# S7CAS-PLEIADES-CARTE-MERE_P06_MISC.net
KiCad netlist of a schematic drawn in Altium Designer
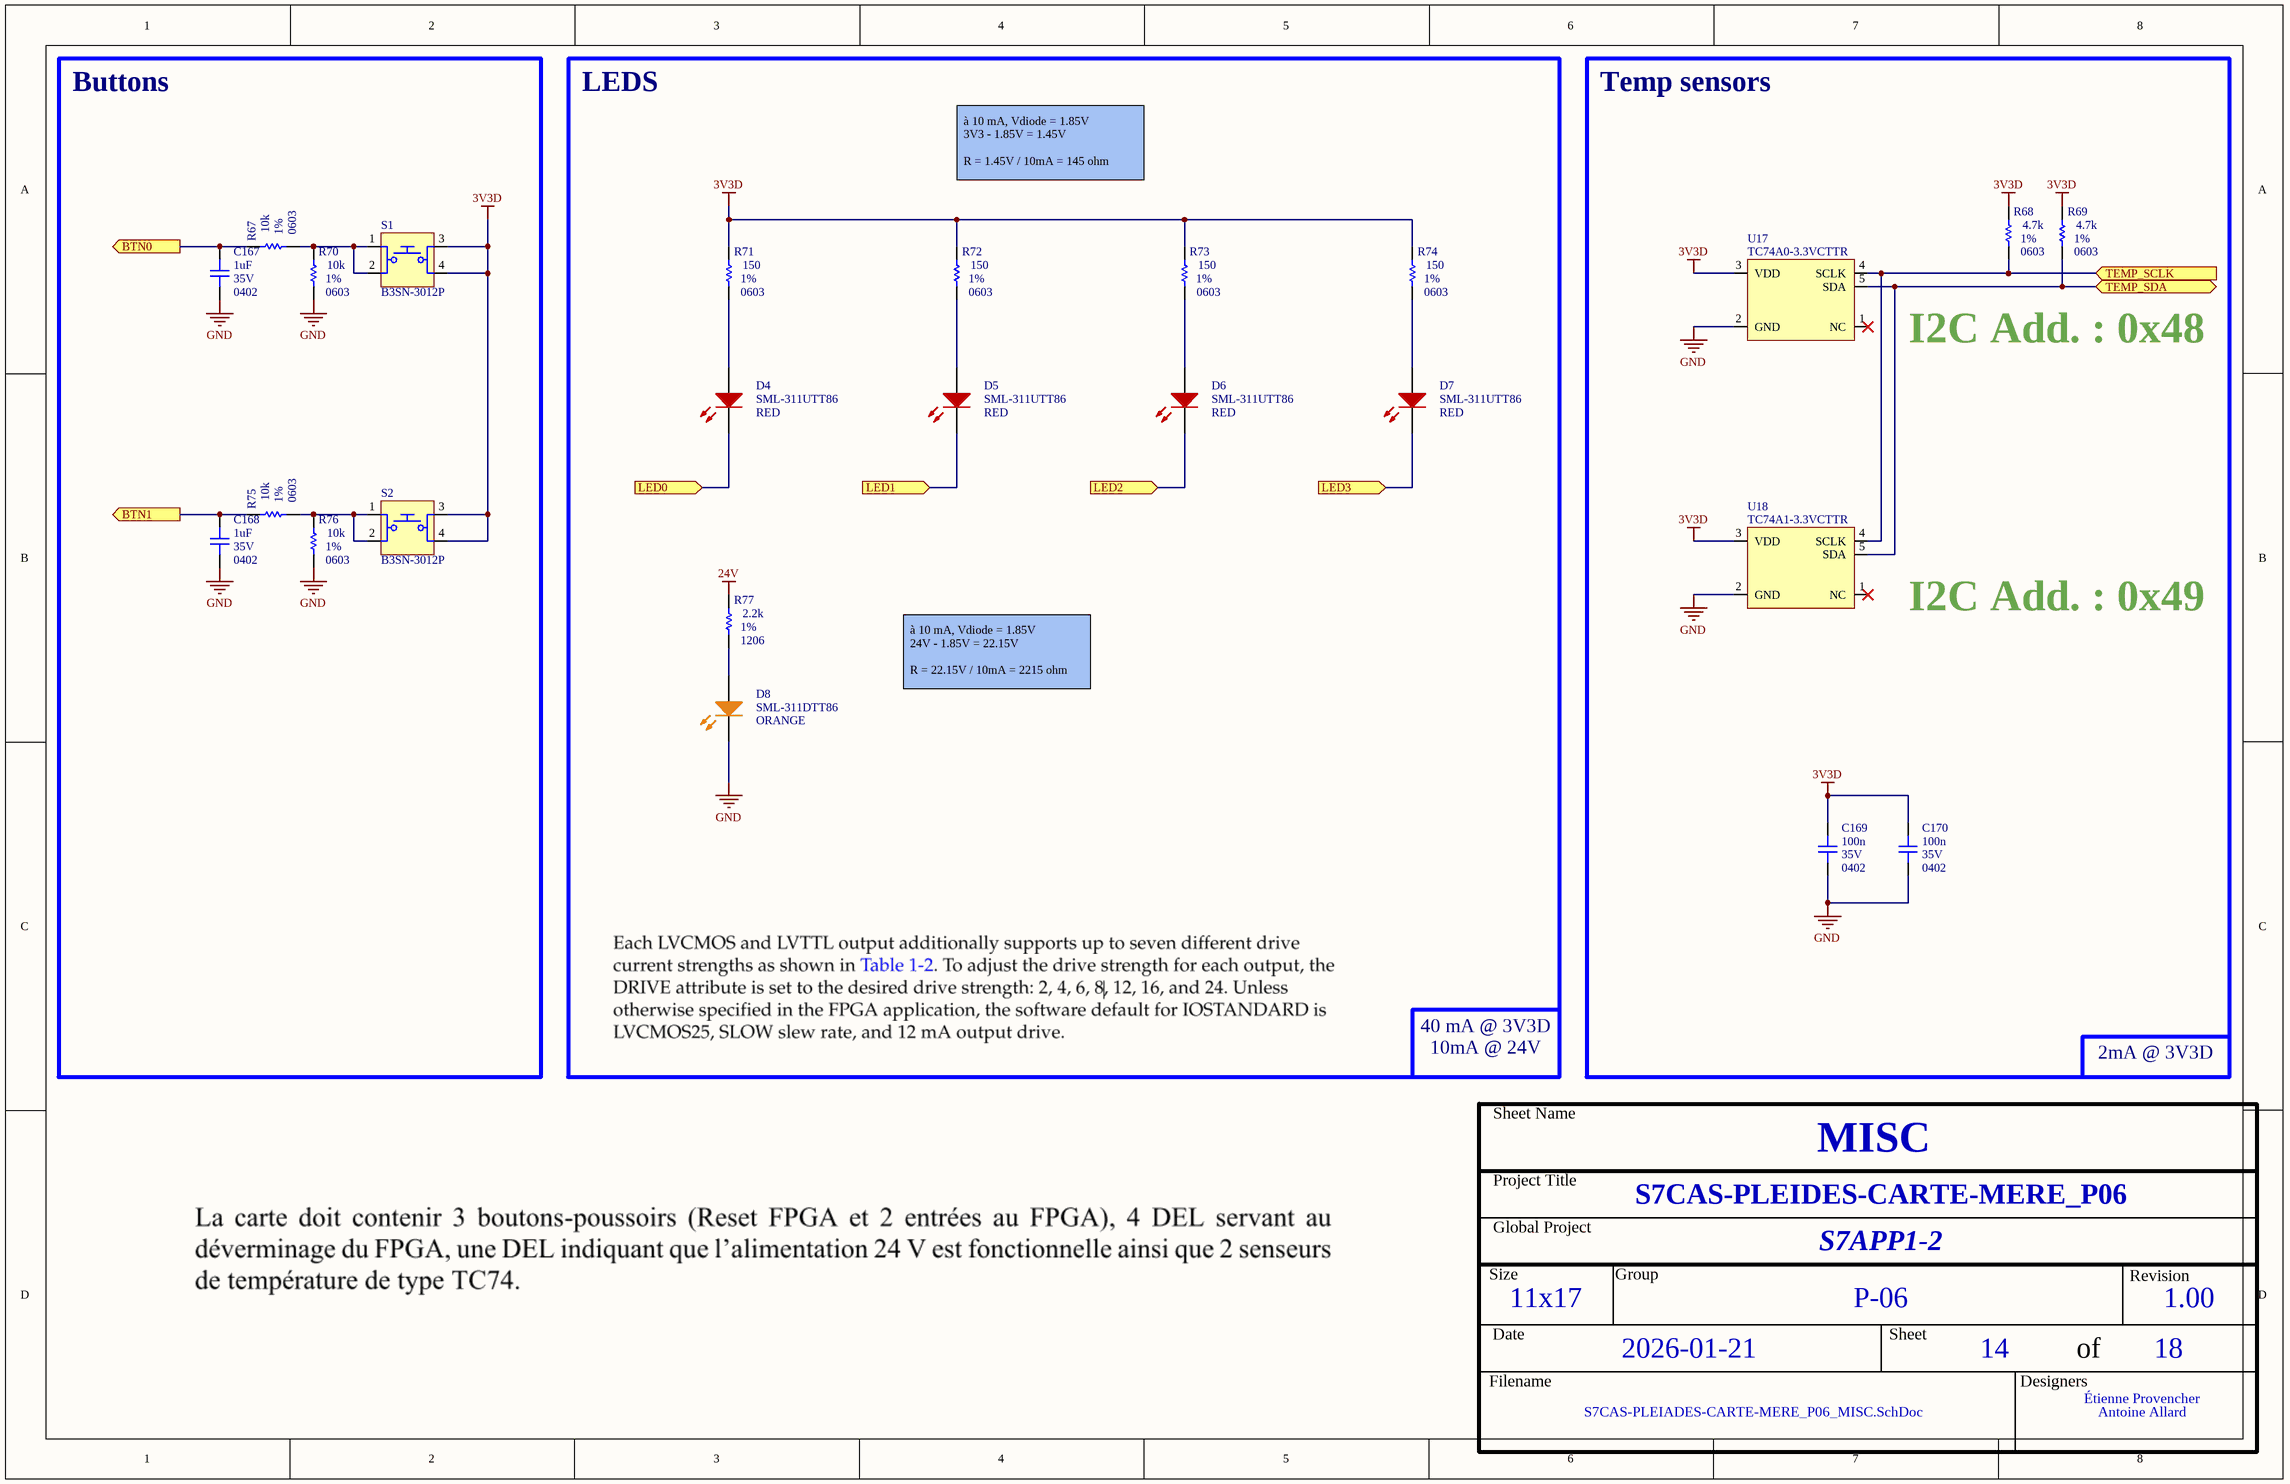
[diagram p0: S7CAS-PLEIADES-CARTE-MERE_P06_MISC.SchDoc]

(export (version "E")
  (design (tool "Eeschema 10.0.6"))
  (components
    (comp (ref "C167")
      (value "1uF")
      (footprint "CAP_0402")
      (description "CAP - 0402")
      (fields
        (field (name "VOLTAGE") "35V")
        (field (name "PACKAGE") "0402")
        (field (name "CREATEDBY") "Jonathan Bouchard")
      )
      (libsource (lib "s7cas_lib2023") (part "CAP - 0402"))
    )
    (comp (ref "C168")
      (value "1uF")
      (footprint "CAP_0402")
      (description "CAP - 0402")
      (fields
        (field (name "VOLTAGE") "35V")
        (field (name "PACKAGE") "0402")
        (field (name "CREATEDBY") "Jonathan Bouchard")
      )
      (libsource (lib "s7cas_lib2023") (part "CAP - 0402"))
    )
    (comp (ref "C169")
      (value "100n")
      (footprint "CAP_0402")
      (description "CAP - 0402")
      (fields
        (field (name "VOLTAGE") "35V")
        (field (name "PACKAGE") "0402")
        (field (name "CREATEDBY") "Jonathan Bouchard")
      )
      (libsource (lib "s7cas_lib2023") (part "CAP - 0402"))
    )
    (comp (ref "C170")
      (value "100n")
      (footprint "CAP_0402")
      (description "CAP - 0402")
      (fields
        (field (name "VOLTAGE") "35V")
        (field (name "PACKAGE") "0402")
        (field (name "CREATEDBY") "Jonathan Bouchard")
      )
      (libsource (lib "s7cas_lib2023") (part "CAP - 0402"))
    )
    (comp (ref "D4")
      (value "SML-311UTT86")
      (footprint "LED_0603")
      (description "LED - 620nM RED 2mA - 0603")
      (fields
        (field (name "VOLTAGE") "1.8V")
        (field (name "MFG") "ROHM Semiconductor")
        (field (name "ALTIUM_VALUE") "RED")
        (field (name "CREATEDBY") "Jonathan Bouchard")
      )
      (libsource (lib "s7cas_lib2023") (part "LED_SML-311UTT86"))
    )
    (comp (ref "D5")
      (value "SML-311UTT86")
      (footprint "LED_0603")
      (description "LED - 620nM RED 2mA - 0603")
      (fields
        (field (name "VOLTAGE") "1.8V")
        (field (name "MFG") "ROHM Semiconductor")
        (field (name "ALTIUM_VALUE") "RED")
        (field (name "CREATEDBY") "Jonathan Bouchard")
      )
      (libsource (lib "s7cas_lib2023") (part "LED_SML-311UTT86"))
    )
    (comp (ref "D6")
      (value "SML-311UTT86")
      (footprint "LED_0603")
      (description "LED - 620nM RED 2mA - 0603")
      (fields
        (field (name "VOLTAGE") "1.8V")
        (field (name "MFG") "ROHM Semiconductor")
        (field (name "ALTIUM_VALUE") "RED")
        (field (name "CREATEDBY") "Jonathan Bouchard")
      )
      (libsource (lib "s7cas_lib2023") (part "LED_SML-311UTT86"))
    )
    (comp (ref "D7")
      (value "SML-311UTT86")
      (footprint "LED_0603")
      (description "LED - 620nM RED 2mA - 0603")
      (fields
        (field (name "VOLTAGE") "1.8V")
        (field (name "MFG") "ROHM Semiconductor")
        (field (name "ALTIUM_VALUE") "RED")
        (field (name "CREATEDBY") "Jonathan Bouchard")
      )
      (libsource (lib "s7cas_lib2023") (part "LED_SML-311UTT86"))
    )
    (comp (ref "D8")
      (value "SML-311DTT86")
      (footprint "LED_0603")
      (description "LED - 611nM ORANGE 2mA - 0603")
      (fields
        (field (name "VOLTAGE") "1.8V")
        (field (name "MFG") "ROHM Semiconductor")
        (field (name "ALTIUM_VALUE") "ORANGE")
        (field (name "CREATEDBY") "Jonathan Bouchard")
      )
      (libsource (lib "s7cas_lib2023") (part "LED_SML-311DTT86"))
    )
    (comp (ref "R67")
      (value "10k")
      (footprint "RES_0603")
      (description "RES - 0603")
      (fields
        (field (name "PACKAGE") "0603")
        (field (name "PRECISION") "1%")
        (field (name "CREATEDBY") "Jonathan Bouchard")
      )
      (libsource (lib "s7cas_lib2023") (part "RES - 0603"))
    )
    (comp (ref "R68")
      (value "4.7k")
      (footprint "RES_0603")
      (description "RES - 0603")
      (fields
        (field (name "PACKAGE") "0603")
        (field (name "PRECISION") "1%")
        (field (name "CREATEDBY") "Jonathan Bouchard")
      )
      (libsource (lib "s7cas_lib2023") (part "RES - 0603"))
    )
    (comp (ref "R69")
      (value "4.7k")
      (footprint "RES_0603")
      (description "RES - 0603")
      (fields
        (field (name "PACKAGE") "0603")
        (field (name "PRECISION") "1%")
        (field (name "CREATEDBY") "Jonathan Bouchard")
      )
      (libsource (lib "s7cas_lib2023") (part "RES - 0603"))
    )
    (comp (ref "R70")
      (value "10k")
      (footprint "RES_0603")
      (description "RES - 0603")
      (fields
        (field (name "PACKAGE") "0603")
        (field (name "PRECISION") "1%")
        (field (name "CREATEDBY") "Jonathan Bouchard")
      )
      (libsource (lib "s7cas_lib2023") (part "RES - 0603"))
    )
    (comp (ref "R71")
      (value "150")
      (footprint "RES_0603")
      (description "RES - 0603")
      (fields
        (field (name "PACKAGE") "0603")
        (field (name "PRECISION") "1%")
        (field (name "CREATEDBY") "Jonathan Bouchard")
      )
      (libsource (lib "s7cas_lib2023") (part "RES - 0603"))
    )
    (comp (ref "R72")
      (value "150")
      (footprint "RES_0603")
      (description "RES - 0603")
      (fields
        (field (name "PACKAGE") "0603")
        (field (name "PRECISION") "1%")
        (field (name "CREATEDBY") "Jonathan Bouchard")
      )
      (libsource (lib "s7cas_lib2023") (part "RES - 0603"))
    )
    (comp (ref "R73")
      (value "150")
      (footprint "RES_0603")
      (description "RES - 0603")
      (fields
        (field (name "PACKAGE") "0603")
        (field (name "PRECISION") "1%")
        (field (name "CREATEDBY") "Jonathan Bouchard")
      )
      (libsource (lib "s7cas_lib2023") (part "RES - 0603"))
    )
    (comp (ref "R74")
      (value "150")
      (footprint "RES_0603")
      (description "RES - 0603")
      (fields
        (field (name "PACKAGE") "0603")
        (field (name "PRECISION") "1%")
        (field (name "CREATEDBY") "Jonathan Bouchard")
      )
      (libsource (lib "s7cas_lib2023") (part "RES - 0603"))
    )
    (comp (ref "R75")
      (value "10k")
      (footprint "RES_0603")
      (description "RES - 0603")
      (fields
        (field (name "PACKAGE") "0603")
        (field (name "PRECISION") "1%")
        (field (name "CREATEDBY") "Jonathan Bouchard")
      )
      (libsource (lib "s7cas_lib2023") (part "RES - 0603"))
    )
    (comp (ref "R76")
      (value "10k")
      (footprint "RES_0603")
      (description "RES - 0603")
      (fields
        (field (name "PACKAGE") "0603")
        (field (name "PRECISION") "1%")
        (field (name "CREATEDBY") "Jonathan Bouchard")
      )
      (libsource (lib "s7cas_lib2023") (part "RES - 0603"))
    )
    (comp (ref "R77")
      (value "2.2k")
      (footprint "RES_1206")
      (description "RES - 1206")
      (fields
        (field (name "POWER") "0.4W")
        (field (name "PACKAGE") "1206")
        (field (name "PRECISION") "1%")
        (field (name "CREATEDBY") "Jonathan Bouchard")
      )
      (libsource (lib "s7cas_lib2023") (part "RES - 1206"))
    )
    (comp (ref "S1")
      (value "B3SN-3012P")
      (footprint "SWI_TACT_B3SN-3012P")
      (description "SWI - SWITCH TACTILE SPST-NO 0.05A 24V -SMD")
      (fields
        (field (name "CREATEDBY/DATE") "Olivier Bernard / 5/12/2017")
        (field (name "VERIFIEDBY") "Caroline Paulin / 11 juillet 2018")
      )
      (libsource (lib "s7cas_lib2023") (part "SWI_TACT_B3SN-3012P_1"))
    )
    (comp (ref "S2")
      (value "B3SN-3012P")
      (footprint "SWI_TACT_B3SN-3012P")
      (description "SWI - SWITCH TACTILE SPST-NO 0.05A 24V -SMD")
      (fields
        (field (name "CREATEDBY/DATE") "Olivier Bernard / 5/12/2017")
        (field (name "VERIFIEDBY") "Caroline Paulin / 11 juillet 2018")
      )
      (libsource (lib "s7cas_lib2023") (part "SWI_TACT_B3SN-3012P_1"))
    )
    (comp (ref "U17")
      (value "TC74A0-3.3VCTTR")
      (footprint "SEN_TEMP_TC74A0-3.3VCTTR")
      (description "SENS - TEMPERATURE SENSOR I2C/SMBUS - SOT23-5")
      (fields
        (field (name "VOLTAGE") "2.7 V ~ 5.5 V")
        (field (name "MFG") "Microchip")
        (field (name "CREATEDBY") "Jonathan Bouchard")
      )
      (libsource (lib "s7cas_lib2023") (part "SENS_TEMP_TC74A0-3.3VCTTR"))
    )
    (comp (ref "U18")
      (value "TC74A1-3.3VCTTR")
      (footprint "SEN_TEMP_TC74A0-3.3VCTTR")
      (description "SENS - TEMPERATURE SENSOR I2C/SMBUS - SOT23-5")
      (fields
        (field (name "VOLTAGE") "2.7 V ~ 5.5 V")
        (field (name "MFG") "Microchip")
        (field (name "CREATEDBY") "Jonathan Bouchard")
      )
      (libsource (lib "s7cas_lib2023") (part "SENS_TEMP_TC74A0-3.3VCTTR"))
    )
  )
  (nets
    (net (code "1") (name "/BTN0") (class "Default")
      (node (ref "C167") (pin "2") (pinfunction "2_2") (pintype "passive"))
      (node (ref "R67") (pin "2") (pinfunction "2_2") (pintype "passive"))
    )
    (net (code "2") (name "/BTN1") (class "Default")
      (node (ref "C168") (pin "2") (pinfunction "2_2") (pintype "passive"))
      (node (ref "R75") (pin "2") (pinfunction "2_2") (pintype "passive"))
    )
    (net (code "3") (name "/LED0") (class "Default")
      (node (ref "D4") (pin "K") (pinfunction "K_K") (pintype "passive"))
    )
    (net (code "4") (name "/LED1") (class "Default")
      (node (ref "D5") (pin "K") (pinfunction "K_K") (pintype "passive"))
    )
    (net (code "5") (name "/LED2") (class "Default")
      (node (ref "D6") (pin "K") (pinfunction "K_K") (pintype "passive"))
    )
    (net (code "6") (name "/LED3") (class "Default")
      (node (ref "D7") (pin "K") (pinfunction "K_K") (pintype "passive"))
    )
    (net (code "7") (name "/TEMP_SCLK") (class "Default")
      (node (ref "R68") (pin "1") (pinfunction "1_1") (pintype "passive"))
      (node (ref "U17") (pin "4") (pinfunction "SCLK_4") (pintype "passive"))
      (node (ref "U18") (pin "4") (pinfunction "SCLK_4") (pintype "passive"))
    )
    (net (code "8") (name "/TEMP_SDA") (class "Default")
      (node (ref "R69") (pin "1") (pinfunction "1_1") (pintype "passive"))
      (node (ref "U17") (pin "5") (pinfunction "SDA_5") (pintype "passive"))
      (node (ref "U18") (pin "5") (pinfunction "SDA_5") (pintype "passive"))
    )
    (net (code "9") (name "3V3D") (class "Default")
      (node (ref "C169") (pin "2") (pinfunction "2_2") (pintype "passive"))
      (node (ref "C170") (pin "2") (pinfunction "2_2") (pintype "passive"))
      (node (ref "R68") (pin "2") (pinfunction "2_2") (pintype "passive"))
      (node (ref "R69") (pin "2") (pinfunction "2_2") (pintype "passive"))
      (node (ref "R71") (pin "2") (pinfunction "2_2") (pintype "passive"))
      (node (ref "R72") (pin "2") (pinfunction "2_2") (pintype "passive"))
      (node (ref "R73") (pin "2") (pinfunction "2_2") (pintype "passive"))
      (node (ref "R74") (pin "2") (pinfunction "2_2") (pintype "passive"))
      (node (ref "S1") (pin "3") (pinfunction "3_3") (pintype "passive"))
      (node (ref "S1") (pin "4") (pinfunction "4_4") (pintype "passive"))
      (node (ref "S2") (pin "3") (pinfunction "3_3") (pintype "passive"))
      (node (ref "S2") (pin "4") (pinfunction "4_4") (pintype "passive"))
      (node (ref "U17") (pin "3") (pinfunction "VDD_3") (pintype "passive"))
      (node (ref "U18") (pin "3") (pinfunction "VDD_3") (pintype "passive"))
    )
    (net (code "10") (name "24V") (class "Default")
      (node (ref "R77") (pin "2") (pinfunction "2_2") (pintype "passive"))
    )
    (net (code "11") (name "GND") (class "Default")
      (node (ref "C167") (pin "1") (pinfunction "1_1") (pintype "passive"))
      (node (ref "C168") (pin "1") (pinfunction "1_1") (pintype "passive"))
      (node (ref "C169") (pin "1") (pinfunction "1_1") (pintype "passive"))
      (node (ref "C170") (pin "1") (pinfunction "1_1") (pintype "passive"))
      (node (ref "D8") (pin "K") (pinfunction "K_K") (pintype "passive"))
      (node (ref "R70") (pin "1") (pinfunction "1_1") (pintype "passive"))
      (node (ref "R76") (pin "1") (pinfunction "1_1") (pintype "passive"))
      (node (ref "U17") (pin "2") (pinfunction "GND_2") (pintype "passive"))
      (node (ref "U18") (pin "2") (pinfunction "GND_2") (pintype "passive"))
    )
    (net (code "12") (name "Net-(D4-PadA)") (class "Default")
      (node (ref "D4") (pin "A") (pinfunction "A_A") (pintype "passive"))
      (node (ref "R71") (pin "1") (pinfunction "1_1") (pintype "passive"))
    )
    (net (code "13") (name "Net-(D5-PadA)") (class "Default")
      (node (ref "D5") (pin "A") (pinfunction "A_A") (pintype "passive"))
      (node (ref "R72") (pin "1") (pinfunction "1_1") (pintype "passive"))
    )
    (net (code "14") (name "Net-(D6-PadA)") (class "Default")
      (node (ref "D6") (pin "A") (pinfunction "A_A") (pintype "passive"))
      (node (ref "R73") (pin "1") (pinfunction "1_1") (pintype "passive"))
    )
    (net (code "15") (name "Net-(D7-PadA)") (class "Default")
      (node (ref "D7") (pin "A") (pinfunction "A_A") (pintype "passive"))
      (node (ref "R74") (pin "1") (pinfunction "1_1") (pintype "passive"))
    )
    (net (code "16") (name "Net-(D8-PadA)") (class "Default")
      (node (ref "D8") (pin "A") (pinfunction "A_A") (pintype "passive"))
      (node (ref "R77") (pin "1") (pinfunction "1_1") (pintype "passive"))
    )
    (net (code "17") (name "Net-(R67-Pad1)") (class "Default")
      (node (ref "R67") (pin "1") (pinfunction "1_1") (pintype "passive"))
      (node (ref "R70") (pin "2") (pinfunction "2_2") (pintype "passive"))
      (node (ref "S1") (pin "1") (pinfunction "1_1") (pintype "passive"))
      (node (ref "S1") (pin "2") (pinfunction "2_2") (pintype "passive"))
    )
    (net (code "18") (name "Net-(R75-Pad1)") (class "Default")
      (node (ref "R75") (pin "1") (pinfunction "1_1") (pintype "passive"))
      (node (ref "R76") (pin "2") (pinfunction "2_2") (pintype "passive"))
      (node (ref "S2") (pin "1") (pinfunction "1_1") (pintype "passive"))
      (node (ref "S2") (pin "2") (pinfunction "2_2") (pintype "passive"))
    )
    (net (code "19") (name "unconnected-(U17-NC-Pad1)") (class "Default")
      (node (ref "U17") (pin "1") (pinfunction "NC_1") (pintype "passive+no_connect"))
    )
    (net (code "20") (name "unconnected-(U18-NC-Pad1)") (class "Default")
      (node (ref "U18") (pin "1") (pinfunction "NC_1") (pintype "passive+no_connect"))
    )
  )
)
